# LINE.net
KiCad netlist of a schematic drawn in EAGLE
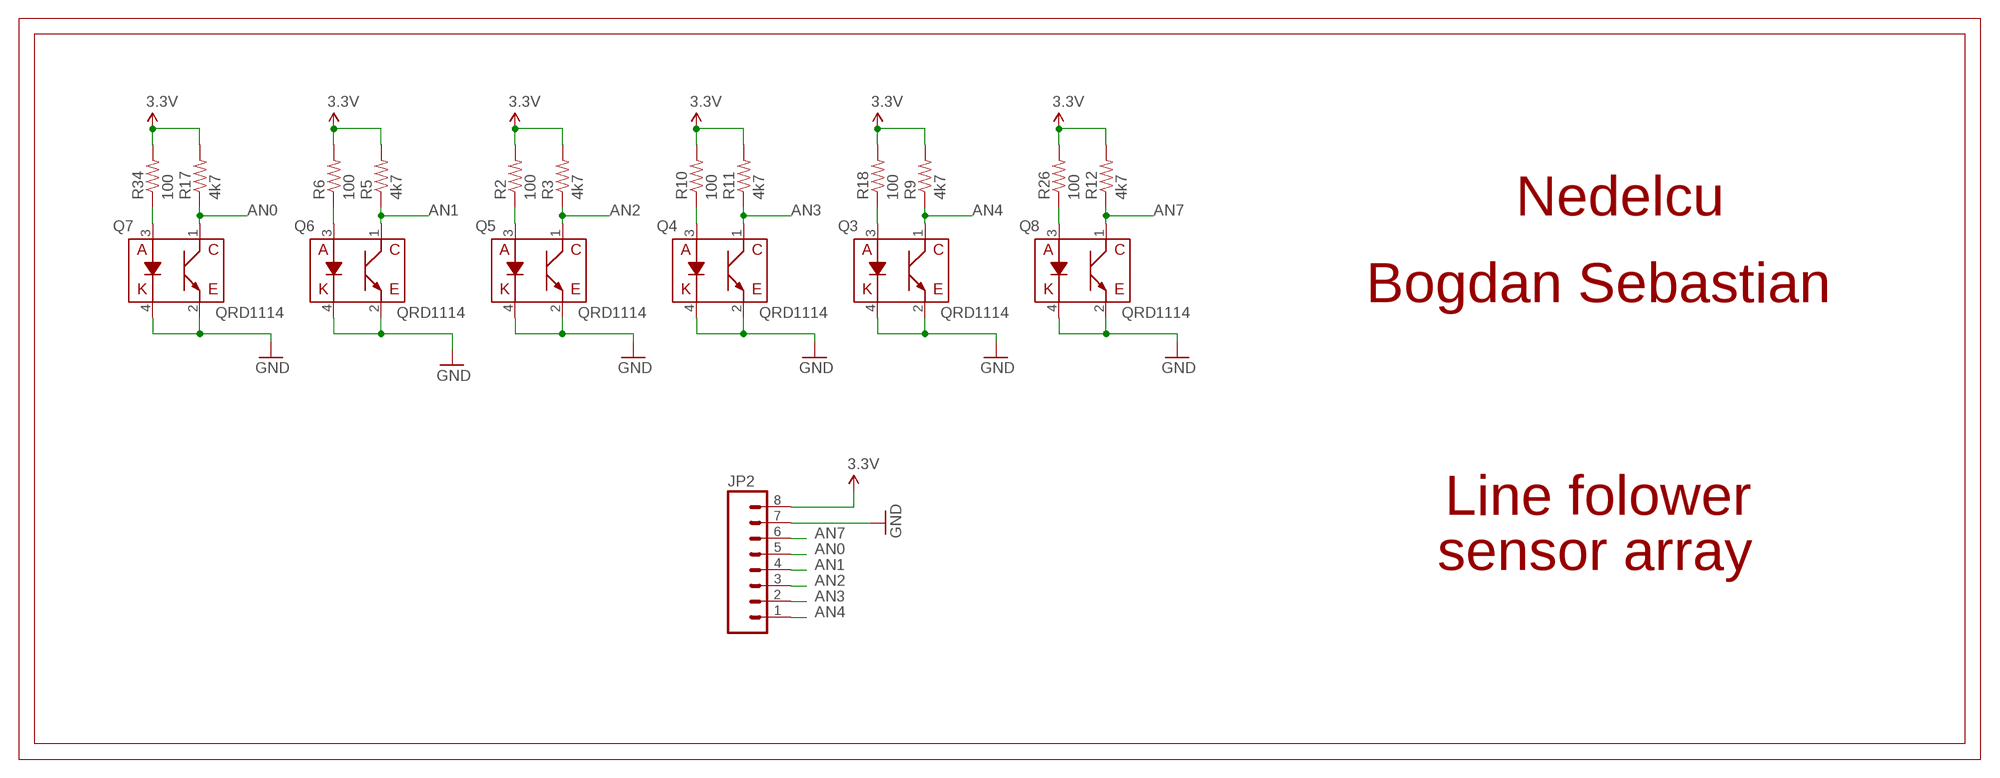
[diagram p0: schematic, sheet 1]

(export (version "E")
  (design (tool "Eeschema 10.0.6"))
  (components
    (comp (ref "JP2")
      (value "M081X08")
      (footprint "eagle-import:1X08")
      (libsource (lib "eagle-import") (part "M081X08"))
    )
    (comp (ref "Q3")
      (value "QRD1114")
      (footprint "eagle-import:QRD1114")
      (libsource (lib "eagle-import") (part "QRD1114"))
    )
    (comp (ref "Q4")
      (value "QRD1114")
      (footprint "eagle-import:QRD1114")
      (libsource (lib "eagle-import") (part "QRD1114"))
    )
    (comp (ref "Q5")
      (value "QRD1114")
      (footprint "eagle-import:QRD1114")
      (libsource (lib "eagle-import") (part "QRD1114"))
    )
    (comp (ref "Q6")
      (value "QRD1114")
      (footprint "eagle-import:QRD1114")
      (libsource (lib "eagle-import") (part "QRD1114"))
    )
    (comp (ref "Q7")
      (value "QRD1114")
      (footprint "eagle-import:QRD1114")
      (libsource (lib "eagle-import") (part "QRD1114"))
    )
    (comp (ref "Q8")
      (value "QRD1114")
      (footprint "eagle-import:QRD1114")
      (libsource (lib "eagle-import") (part "QRD1114"))
    )
    (comp (ref "R2")
      (value "100")
      (footprint "eagle-import:0805")
      (libsource (lib "eagle-import") (part "RESISTOR0805-RES"))
    )
    (comp (ref "R3")
      (value "4k7")
      (footprint "eagle-import:0805")
      (libsource (lib "eagle-import") (part "RESISTOR0805-RES"))
    )
    (comp (ref "R5")
      (value "4k7")
      (footprint "eagle-import:0805")
      (libsource (lib "eagle-import") (part "RESISTOR0805-RES"))
    )
    (comp (ref "R6")
      (value "100")
      (footprint "eagle-import:0805")
      (libsource (lib "eagle-import") (part "RESISTOR0805-RES"))
    )
    (comp (ref "R9")
      (value "4k7")
      (footprint "eagle-import:0805")
      (libsource (lib "eagle-import") (part "RESISTOR0805-RES"))
    )
    (comp (ref "R10")
      (value "100")
      (footprint "eagle-import:0805")
      (libsource (lib "eagle-import") (part "RESISTOR0805-RES"))
    )
    (comp (ref "R11")
      (value "4k7")
      (footprint "eagle-import:0805")
      (libsource (lib "eagle-import") (part "RESISTOR0805-RES"))
    )
    (comp (ref "R12")
      (value "4k7")
      (footprint "eagle-import:0805")
      (libsource (lib "eagle-import") (part "RESISTOR0805-RES"))
    )
    (comp (ref "R17")
      (value "4k7")
      (footprint "eagle-import:0805")
      (libsource (lib "eagle-import") (part "RESISTOR0805-RES"))
    )
    (comp (ref "R18")
      (value "100")
      (footprint "eagle-import:0805")
      (libsource (lib "eagle-import") (part "RESISTOR0805-RES"))
    )
    (comp (ref "R26")
      (value "100")
      (footprint "eagle-import:0805")
      (libsource (lib "eagle-import") (part "RESISTOR0805-RES"))
    )
    (comp (ref "R34")
      (value "100")
      (footprint "eagle-import:0805")
      (libsource (lib "eagle-import") (part "RESISTOR0805-RES"))
    )
  )
  (nets
    (net (code "1") (name "/AN0") (class "Default")
      (node (ref "JP2") (pin "5") (pinfunction "5_5") (pintype "passive"))
      (node (ref "Q7") (pin "1") (pinfunction "E_1") (pintype "bidirectional"))
      (node (ref "R17") (pin "1") (pinfunction "1_1") (pintype "passive"))
    )
    (net (code "2") (name "/AN1") (class "Default")
      (node (ref "JP2") (pin "4") (pinfunction "4_4") (pintype "passive"))
      (node (ref "Q6") (pin "1") (pinfunction "E_1") (pintype "bidirectional"))
      (node (ref "R5") (pin "1") (pinfunction "1_1") (pintype "passive"))
    )
    (net (code "3") (name "/AN2") (class "Default")
      (node (ref "JP2") (pin "3") (pinfunction "3_3") (pintype "passive"))
      (node (ref "Q5") (pin "1") (pinfunction "E_1") (pintype "bidirectional"))
      (node (ref "R3") (pin "1") (pinfunction "1_1") (pintype "passive"))
    )
    (net (code "4") (name "/AN3") (class "Default")
      (node (ref "JP2") (pin "2") (pinfunction "2_2") (pintype "passive"))
      (node (ref "Q4") (pin "1") (pinfunction "E_1") (pintype "bidirectional"))
      (node (ref "R11") (pin "1") (pinfunction "1_1") (pintype "passive"))
    )
    (net (code "5") (name "/AN4") (class "Default")
      (node (ref "JP2") (pin "1") (pinfunction "1_1") (pintype "passive"))
      (node (ref "Q3") (pin "1") (pinfunction "E_1") (pintype "bidirectional"))
      (node (ref "R9") (pin "1") (pinfunction "1_1") (pintype "passive"))
    )
    (net (code "6") (name "/AN7") (class "Default")
      (node (ref "JP2") (pin "6") (pinfunction "6_6") (pintype "passive"))
      (node (ref "Q8") (pin "1") (pinfunction "E_1") (pintype "bidirectional"))
      (node (ref "R12") (pin "1") (pinfunction "1_1") (pintype "passive"))
    )
    (net (code "7") (name "3.3V") (class "Default")
      (node (ref "JP2") (pin "8") (pinfunction "8_8") (pintype "passive"))
      (node (ref "R10") (pin "2") (pinfunction "2_2") (pintype "passive"))
      (node (ref "R11") (pin "2") (pinfunction "2_2") (pintype "passive"))
      (node (ref "R12") (pin "2") (pinfunction "2_2") (pintype "passive"))
      (node (ref "R17") (pin "2") (pinfunction "2_2") (pintype "passive"))
      (node (ref "R18") (pin "2") (pinfunction "2_2") (pintype "passive"))
      (node (ref "R2") (pin "2") (pinfunction "2_2") (pintype "passive"))
      (node (ref "R26") (pin "2") (pinfunction "2_2") (pintype "passive"))
      (node (ref "R3") (pin "2") (pinfunction "2_2") (pintype "passive"))
      (node (ref "R34") (pin "2") (pinfunction "2_2") (pintype "passive"))
      (node (ref "R5") (pin "2") (pinfunction "2_2") (pintype "passive"))
      (node (ref "R6") (pin "2") (pinfunction "2_2") (pintype "passive"))
      (node (ref "R9") (pin "2") (pinfunction "2_2") (pintype "passive"))
    )
    (net (code "8") (name "GND") (class "Default")
      (node (ref "JP2") (pin "7") (pinfunction "7_7") (pintype "passive"))
      (node (ref "Q3") (pin "2") (pinfunction "C_2") (pintype "bidirectional"))
      (node (ref "Q3") (pin "4") (pinfunction "K_4") (pintype "bidirectional"))
      (node (ref "Q4") (pin "2") (pinfunction "C_2") (pintype "bidirectional"))
      (node (ref "Q4") (pin "4") (pinfunction "K_4") (pintype "bidirectional"))
      (node (ref "Q5") (pin "2") (pinfunction "C_2") (pintype "bidirectional"))
      (node (ref "Q5") (pin "4") (pinfunction "K_4") (pintype "bidirectional"))
      (node (ref "Q6") (pin "2") (pinfunction "C_2") (pintype "bidirectional"))
      (node (ref "Q6") (pin "4") (pinfunction "K_4") (pintype "bidirectional"))
      (node (ref "Q7") (pin "2") (pinfunction "C_2") (pintype "bidirectional"))
      (node (ref "Q7") (pin "4") (pinfunction "K_4") (pintype "bidirectional"))
      (node (ref "Q8") (pin "2") (pinfunction "C_2") (pintype "bidirectional"))
      (node (ref "Q8") (pin "4") (pinfunction "K_4") (pintype "bidirectional"))
    )
    (net (code "9") (name "Net-(Q3-A)") (class "Default")
      (node (ref "Q3") (pin "3") (pinfunction "A_3") (pintype "bidirectional"))
      (node (ref "R18") (pin "1") (pinfunction "1_1") (pintype "passive"))
    )
    (net (code "10") (name "Net-(Q4-A)") (class "Default")
      (node (ref "Q4") (pin "3") (pinfunction "A_3") (pintype "bidirectional"))
      (node (ref "R10") (pin "1") (pinfunction "1_1") (pintype "passive"))
    )
    (net (code "11") (name "Net-(Q5-A)") (class "Default")
      (node (ref "Q5") (pin "3") (pinfunction "A_3") (pintype "bidirectional"))
      (node (ref "R2") (pin "1") (pinfunction "1_1") (pintype "passive"))
    )
    (net (code "12") (name "Net-(Q6-A)") (class "Default")
      (node (ref "Q6") (pin "3") (pinfunction "A_3") (pintype "bidirectional"))
      (node (ref "R6") (pin "1") (pinfunction "1_1") (pintype "passive"))
    )
    (net (code "13") (name "Net-(Q7-A)") (class "Default")
      (node (ref "Q7") (pin "3") (pinfunction "A_3") (pintype "bidirectional"))
      (node (ref "R34") (pin "1") (pinfunction "1_1") (pintype "passive"))
    )
    (net (code "14") (name "Net-(Q8-A)") (class "Default")
      (node (ref "Q8") (pin "3") (pinfunction "A_3") (pintype "bidirectional"))
      (node (ref "R26") (pin "1") (pinfunction "1_1") (pintype "passive"))
    )
  )
)
